# L293DbaseArduVehicle-ElectricalSchematic.net
KiCad netlist of a schematic drawn in Altium Designer
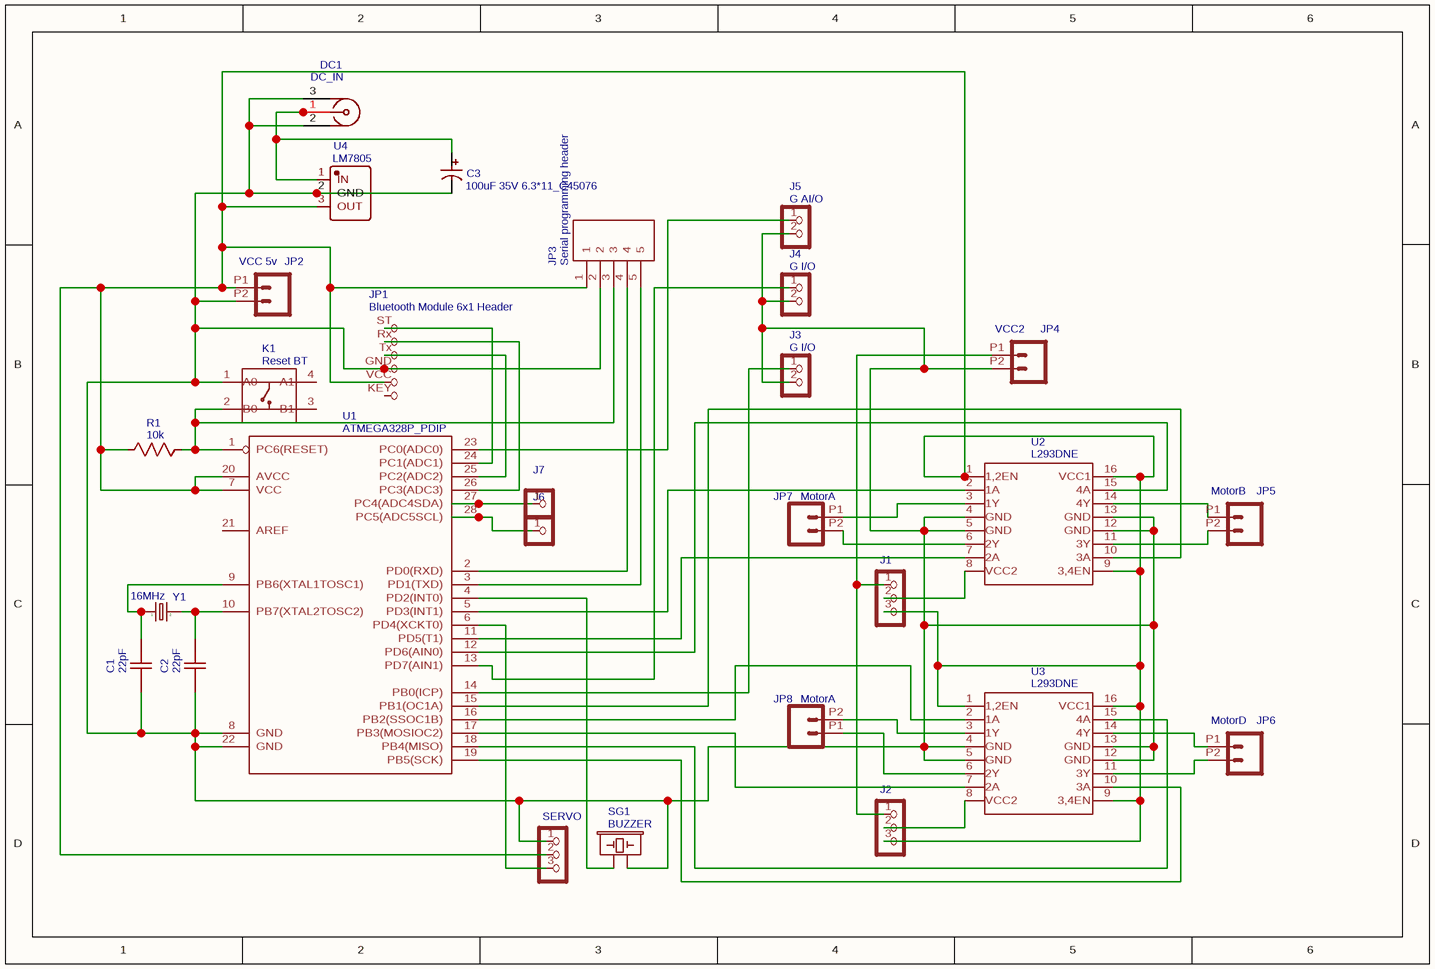
[diagram p0: L293DbaseArduVehicle-ElectricalSchematic_2022-03-31.schdoc]

(export (version "E")
  (design (tool "Eeschema 10.0.6"))
  (components
    (comp (ref "C1")
      (value "22pF")
      (fields (field (name "BOM_MANUFACTURER PART") "?"))
      (libsource (lib "altium-import") (part "root_1_22pF_"))
    )
    (comp (ref "C2")
      (value "22pF")
      (fields (field (name "BOM_MANUFACTURER PART") "?"))
      (libsource (lib "altium-import") (part "root_1_22pF_"))
    )
    (comp (ref "C3")
      (value "100uF 35V 6.3*11_C45076")
      (fields
        (field (name "BOM_SUPPLIER PART") "C45076")
        (field (name "BOM_MANUFACTURER PART") "100uF 35V 6.3*11")
      )
      (libsource (lib "altium-import") (part "root_3_100uF 35V 6.3*11_C45076_"))
    )
    (comp (ref "DC1")
      (value "DC_IN")
      (fields (field (name "BOM_MANUFACTURER PART") "DC005-2.0MM") (field (name "CONTRIBUTOR") "KKHOME生活"))
      (libsource (lib "altium-import") (part "root_0_DC_IN_"))
    )
    (comp (ref "J1")
      (value "CON_HEADER_1X03-PTH")
      (fields (field (name "BOM_MANUFACTURER PART") "?") (field (name "CONTRIBUTOR") "DangerousPrototype"))
      (libsource (lib "altium-import") (part "root_0_CON_HEADER_1X03-PTH_"))
    )
    (comp (ref "J2")
      (value "CON_HEADER_1X03-PTH")
      (fields (field (name "BOM_MANUFACTURER PART") "?") (field (name "CONTRIBUTOR") "DangerousPrototype"))
      (libsource (lib "altium-import") (part "root_0_CON_HEADER_1X03-PTH_"))
    )
    (comp (ref "J3")
      (value "G I/O")
      (fields (field (name "BOM_MANUFACTURER PART") "?") (field (name "CONTRIBUTOR") "DangerousPrototype"))
      (libsource (lib "altium-import") (part "root_0_G I/O_"))
    )
    (comp (ref "J4")
      (value "G I/O")
      (fields (field (name "BOM_MANUFACTURER PART") "?") (field (name "CONTRIBUTOR") "DangerousPrototype"))
      (libsource (lib "altium-import") (part "root_0_G I/O_"))
    )
    (comp (ref "J5")
      (value "G AI/O")
      (fields (field (name "BOM_MANUFACTURER PART") "?") (field (name "CONTRIBUTOR") "DangerousPrototype"))
      (libsource (lib "altium-import") (part "root_0_G AI/O_"))
    )
    (comp (ref "J6")
      (value "CON_HEADER_1X01-PTH")
      (fields (field (name "BOM_MANUFACTURER PART") "?") (field (name "CONTRIBUTOR") "DangerousPrototype"))
      (libsource (lib "altium-import") (part "root_0_CON_HEADER_1X01-PTH_"))
    )
    (comp (ref "J7")
      (value "CON_HEADER_1X01-PTH")
      (fields (field (name "BOM_MANUFACTURER PART") "?") (field (name "CONTRIBUTOR") "DangerousPrototype"))
      (libsource (lib "altium-import") (part "root_0_CON_HEADER_1X01-PTH_"))
    )
    (comp (ref "JP1")
      (value "Bluetooth Module 6x1 Header")
      (description "PIN HEADER")
      (fields (field (name "BOM_MANUFACTURER PART") "?") (field (name "CONTRIBUTOR") "Adafruit"))
      (libsource (lib "altium-import") (part "root_0_Bluetooth Module 6x1 Header_"))
    )
    (comp (ref "JP2")
      (value "VCC 5v")
      (description "Standard 2-pin 0.1 header. Use with")
      (fields (field (name "BOM_MANUFACTURER PART") "?") (field (name "CONTRIBUTOR") "SparkFun"))
      (libsource (lib "altium-import") (part "root_2_VCC 5v_"))
    )
    (comp (ref "JP3")
      (value "Serial programming header")
      (fields (field (name "BOM_MANUFACTURER PART") "?"))
      (libsource (lib "altium-import") (part "root_1_Serial programming header_"))
    )
    (comp (ref "JP4")
      (value "VCC2")
      (description "Standard 2-pin 0.1 header. Use with")
      (fields (field (name "BOM_MANUFACTURER PART") "?") (field (name "CONTRIBUTOR") "SparkFun"))
      (libsource (lib "altium-import") (part "root_2_VCC2_"))
    )
    (comp (ref "JP5")
      (value "MotorB")
      (description "Standard 2-pin 0.1 header. Use with")
      (fields (field (name "BOM_MANUFACTURER PART") "?") (field (name "CONTRIBUTOR") "SparkFun"))
      (libsource (lib "altium-import") (part "root_2_MotorB_"))
    )
    (comp (ref "JP6")
      (value "MotorD")
      (description "Standard 2-pin 0.1 header. Use with")
      (fields (field (name "BOM_MANUFACTURER PART") "?") (field (name "CONTRIBUTOR") "SparkFun"))
      (libsource (lib "altium-import") (part "root_2_MotorD_"))
    )
    (comp (ref "JP7")
      (value "MotorA")
      (description "Standard 2-pin 0.1 header. Use with")
      (fields (field (name "BOM_MANUFACTURER PART") "?") (field (name "CONTRIBUTOR") "SparkFun"))
      (libsource (lib "") (part "root_2_MotorA__1"))
    )
    (comp (ref "JP8")
      (value "MotorA")
      (description "Standard 2-pin 0.1 header. Use with")
      (fields (field (name "BOM_MANUFACTURER PART") "?") (field (name "CONTRIBUTOR") "SparkFun"))
      (libsource (lib "altium-import") (part "root_2_MotorA_"))
    )
    (comp (ref "K1")
      (value "Reset BT")
      (description "SWITCH TACTILE SPST-NO 0.05A 12V")
      (fields (field (name "BOM_MANUFACTURER PART") "TS-1109") (field (name "BOM_SUPPLIER PART") "311020024"))
      (libsource (lib "altium-import") (part "root_0_Reset BT_"))
    )
    (comp (ref "R1")
      (value "10k")
      (fields (field (name "BOM_MANUFACTURER PART") "?"))
      (libsource (lib "altium-import") (part "root_0_10k_"))
    )
    (comp (ref "SERVO")
      (value "CON_HEADER_1X03-PTH")
      (fields (field (name "BOM_MANUFACTURER PART") "?") (field (name "CONTRIBUTOR") "DangerousPrototype"))
      (libsource (lib "altium-import") (part "root_0_CON_HEADER_1X03-PTH_"))
    )
    (comp (ref "SG1")
      (value "BUZZER")
      (fields (field (name "BOM_MANUFACTURER PART") "?") (field (name "CONTRIBUTOR") "SparkFun"))
      (libsource (lib "altium-import") (part "root_0_BUZZER_"))
    )
    (comp (ref "U1")
      (value "ATMEGA328P_PDIP")
      (description "uC used in the Arduino")
      (fields (field (name "BOM_MANUFACTURER PART") "?") (field (name "CONTRIBUTOR") "SparkFun"))
      (libsource (lib "altium-import") (part "root_0_ATMEGA328P_PDIP_"))
    )
    (comp (ref "U2")
      (value "L293DNE")
      (description "DIP IC Driver;")
      (fields (field (name "BOM_SUPPLIER PART") "310040017"))
      (libsource (lib "altium-import") (part "root_0_L293DNE_"))
    )
    (comp (ref "U3")
      (value "L293DNE")
      (description "DIP IC Driver;")
      (fields (field (name "BOM_SUPPLIER PART") "310040017"))
      (libsource (lib "altium-import") (part "root_0_L293DNE_"))
    )
    (comp (ref "U4")
      (value "LM7805")
      (fields (field (name "BOM_SUPPLIER PART") "C845394") (field (name "CONTRIBUTOR") "LCSC"))
      (libsource (lib "altium-import") (part "root_0_LM7805_"))
    )
    (comp (ref "Y1")
      (value "16MHz")
      (description "DIP Crystal 16MHz-18pF-30ppm-40R;")
      (fields
        (field (name "BOM_MANUFACTURER PART") "HC-49US    16.000MHz")
        (field (name "BOM_SUPPLIER PART") "306010014")
      )
      (libsource (lib "altium-import") (part "root_0_16MHz_"))
    )
  )
  (nets
    (net (code "1") (name "Net-(DC1-GND)") (class "Default")
      (node (ref "C1") (pin "1") (pinfunction "1_1") (pintype "passive"))
      (node (ref "C2") (pin "1") (pinfunction "1_1") (pintype "passive"))
      (node (ref "C3") (pin "2") (pinfunction "2_2") (pintype "passive"))
      (node (ref "DC1") (pin "2") (pinfunction "2_2") (pintype "passive"))
      (node (ref "DC1") (pin "3") (pinfunction "GND_3") (pintype "passive"))
      (node (ref "J3") (pin "2") (pinfunction "2_2") (pintype "passive"))
      (node (ref "J4") (pin "2") (pinfunction "2_2") (pintype "passive"))
      (node (ref "J5") (pin "2") (pinfunction "2_2") (pintype "passive"))
      (node (ref "JP1") (pin "GND") (pinfunction "GND_GND") (pintype "passive"))
      (node (ref "JP2") (pin "P2") (pinfunction "2_P2") (pintype "passive"))
      (node (ref "JP3") (pin "2") (pinfunction "2_2") (pintype "passive"))
      (node (ref "JP4") (pin "P2") (pinfunction "2_P2") (pintype "passive"))
      (node (ref "K1") (pin "1") (pinfunction "A0_1") (pintype "passive"))
      (node (ref "SERVO") (pin "1") (pinfunction "1_1") (pintype "passive"))
      (node (ref "SG1") (pin "-") (pinfunction "2_-") (pintype "passive"))
      (node (ref "U1") (pin "22") (pinfunction "GND_22") (pintype "passive"))
      (node (ref "U1") (pin "8") (pinfunction "GND_8") (pintype "passive"))
      (node (ref "U2") (pin "12") (pinfunction "GND_12") (pintype "passive"))
      (node (ref "U2") (pin "13") (pinfunction "GND_13") (pintype "passive"))
      (node (ref "U2") (pin "4") (pinfunction "GND_4") (pintype "passive"))
      (node (ref "U2") (pin "5") (pinfunction "GND_5") (pintype "passive"))
      (node (ref "U3") (pin "12") (pinfunction "GND_12") (pintype "passive"))
      (node (ref "U3") (pin "13") (pinfunction "GND_13") (pintype "passive"))
      (node (ref "U3") (pin "4") (pinfunction "GND_4") (pintype "passive"))
      (node (ref "U3") (pin "5") (pinfunction "GND_5") (pintype "passive"))
      (node (ref "U4") (pin "2") (pinfunction "GND_2") (pintype "passive"))
    )
    (net (code "2") (name "Net-(DC1-VCC)") (class "Default")
      (node (ref "C3") (pin "1") (pinfunction "1_1") (pintype "passive"))
      (node (ref "DC1") (pin "1") (pinfunction "VCC_1") (pintype "passive"))
      (node (ref "U4") (pin "1") (pinfunction "IN_1") (pintype "passive"))
    )
    (net (code "3") (name "Net-(JP2-1)") (class "Default")
      (node (ref "J1") (pin "3") (pinfunction "3_3") (pintype "passive"))
      (node (ref "J2") (pin "3") (pinfunction "3_3") (pintype "passive"))
      (node (ref "JP1") (pin "VCC") (pinfunction "VCC_VCC") (pintype "passive"))
      (node (ref "JP2") (pin "P1") (pinfunction "1_P1") (pintype "passive"))
      (node (ref "JP3") (pin "1") (pinfunction "1_1") (pintype "passive"))
      (node (ref "R1") (pin "1") (pinfunction "1_1") (pintype "passive"))
      (node (ref "SERVO") (pin "2") (pinfunction "2_2") (pintype "passive"))
      (node (ref "U1") (pin "20") (pinfunction "AVCC_20") (pintype "passive"))
      (node (ref "U1") (pin "7") (pinfunction "VCC_7") (pintype "passive"))
      (node (ref "U2") (pin "1") (pinfunction "1,2EN_1") (pintype "passive"))
      (node (ref "U2") (pin "16") (pinfunction "VCC1_16") (pintype "passive"))
      (node (ref "U2") (pin "9") (pinfunction "3,4EN_9") (pintype "passive"))
      (node (ref "U3") (pin "1") (pinfunction "1,2EN_1") (pintype "passive"))
      (node (ref "U3") (pin "16") (pinfunction "VCC1_16") (pintype "passive"))
      (node (ref "U3") (pin "9") (pinfunction "3,4EN_9") (pintype "passive"))
      (node (ref "U4") (pin "3") (pinfunction "OUT_3") (pintype "passive"))
    )
    (net (code "4") (name "Net-(JP4-1)") (class "Default")
      (node (ref "J1") (pin "1") (pinfunction "1_1") (pintype "passive"))
      (node (ref "J2") (pin "1") (pinfunction "1_1") (pintype "passive"))
      (node (ref "JP4") (pin "P1") (pinfunction "1_P1") (pintype "passive"))
    )
    (net (code "5") (name "Net-(JP5-1)") (class "Default")
      (node (ref "JP5") (pin "P1") (pinfunction "1_P1") (pintype "passive"))
      (node (ref "U2") (pin "14") (pinfunction "4Y_14") (pintype "passive"))
    )
    (net (code "6") (name "Net-(JP5-2)") (class "Default")
      (node (ref "JP5") (pin "P2") (pinfunction "2_P2") (pintype "passive"))
      (node (ref "U2") (pin "11") (pinfunction "3Y_11") (pintype "passive"))
    )
    (net (code "7") (name "Net-(JP6-1)") (class "Default")
      (node (ref "JP6") (pin "P1") (pinfunction "1_P1") (pintype "passive"))
      (node (ref "U3") (pin "14") (pinfunction "4Y_14") (pintype "passive"))
    )
    (net (code "8") (name "Net-(JP6-2)") (class "Default")
      (node (ref "JP6") (pin "P2") (pinfunction "2_P2") (pintype "passive"))
      (node (ref "U3") (pin "11") (pinfunction "3Y_11") (pintype "passive"))
    )
    (net (code "9") (name "Net-(JP7-1)") (class "Default")
      (node (ref "JP7") (pin "P1") (pinfunction "1_P1") (pintype "passive"))
      (node (ref "U2") (pin "3") (pinfunction "1Y_3") (pintype "passive"))
    )
    (net (code "10") (name "Net-(JP7-2)") (class "Default")
      (node (ref "JP7") (pin "P2") (pinfunction "2_P2") (pintype "passive"))
      (node (ref "U2") (pin "6") (pinfunction "2Y_6") (pintype "passive"))
    )
    (net (code "11") (name "Net-(JP8-1)") (class "Default")
      (node (ref "JP8") (pin "P2") (pinfunction "1_P2") (pintype "passive"))
      (node (ref "U3") (pin "3") (pinfunction "1Y_3") (pintype "passive"))
    )
    (net (code "12") (name "Net-(JP8-2)") (class "Default")
      (node (ref "JP8") (pin "P1") (pinfunction "2_P1") (pintype "passive"))
      (node (ref "U3") (pin "6") (pinfunction "2Y_6") (pintype "passive"))
    )
    (net (code "13") (name "Net-(K1-B0)") (class "Default")
      (node (ref "JP3") (pin "3") (pinfunction "3_3") (pintype "passive"))
      (node (ref "K1") (pin "2") (pinfunction "B0_2") (pintype "passive"))
      (node (ref "R1") (pin "2") (pinfunction "2_2") (pintype "passive"))
      (node (ref "U1") (pin "1") (pinfunction "PC6(RESET)_1") (pintype "passive"))
    )
    (net (code "14") (name "Net-(SG1-1)") (class "Default")
      (node (ref "SG1") (pin "+") (pinfunction "1_+") (pintype "passive"))
      (node (ref "U1") (pin "4") (pinfunction "PD2(INT0)_4") (pintype "passive"))
    )
    (net (code "15") (name "Net-(U1-PB0(ICP))") (class "Default")
      (node (ref "J3") (pin "1") (pinfunction "1_1") (pintype "passive"))
      (node (ref "U1") (pin "14") (pinfunction "PB0(ICP)_14") (pintype "passive"))
    )
    (net (code "16") (name "Net-(U1-PB1(OC1A))") (class "Default")
      (node (ref "U1") (pin "15") (pinfunction "PB1(OC1A)_15") (pintype "passive"))
      (node (ref "U2") (pin "10") (pinfunction "3A_10") (pintype "passive"))
    )
    (net (code "17") (name "Net-(U1-PB2(SSOC1B))") (class "Default")
      (node (ref "U1") (pin "16") (pinfunction "PB2(SSOC1B)_16") (pintype "passive"))
      (node (ref "U3") (pin "2") (pinfunction "1A_2") (pintype "passive"))
    )
    (net (code "18") (name "Net-(U1-PB3(MOSIOC2))") (class "Default")
      (node (ref "U1") (pin "17") (pinfunction "PB3(MOSIOC2)_17") (pintype "passive"))
      (node (ref "U3") (pin "7") (pinfunction "2A_7") (pintype "passive"))
    )
    (net (code "19") (name "Net-(U1-PB4(MISO))") (class "Default")
      (node (ref "U1") (pin "18") (pinfunction "PB4(MISO)_18") (pintype "passive"))
      (node (ref "U3") (pin "15") (pinfunction "4A_15") (pintype "passive"))
    )
    (net (code "20") (name "Net-(U1-PB5(SCK))") (class "Default")
      (node (ref "U1") (pin "19") (pinfunction "PB5(SCK)_19") (pintype "passive"))
      (node (ref "U3") (pin "10") (pinfunction "3A_10") (pintype "passive"))
    )
    (net (code "21") (name "Net-(U1-PB6(XTAL1TOSC1))") (class "Default")
      (node (ref "C1") (pin "2") (pinfunction "2_2") (pintype "passive"))
      (node (ref "U1") (pin "9") (pinfunction "PB6(XTAL1TOSC1)_9") (pintype "passive"))
      (node (ref "Y1") (pin "1") (pinfunction "1_1") (pintype "passive"))
    )
    (net (code "22") (name "Net-(U1-PB7(XTAL2TOSC2))") (class "Default")
      (node (ref "C2") (pin "2") (pinfunction "2_2") (pintype "passive"))
      (node (ref "U1") (pin "10") (pinfunction "PB7(XTAL2TOSC2)_10") (pintype "passive"))
      (node (ref "Y1") (pin "2") (pinfunction "2_2") (pintype "passive"))
    )
    (net (code "23") (name "Net-(U1-PC0(ADC0))") (class "Default")
      (node (ref "J5") (pin "1") (pinfunction "1_1") (pintype "passive"))
      (node (ref "U1") (pin "23") (pinfunction "PC0(ADC0)_23") (pintype "passive"))
    )
    (net (code "24") (name "Net-(U1-PC1(ADC1))") (class "Default")
      (node (ref "JP1") (pin "ST") (pinfunction "ST_ST") (pintype "passive"))
      (node (ref "U1") (pin "24") (pinfunction "PC1(ADC1)_24") (pintype "passive"))
    )
    (net (code "25") (name "Net-(U1-PC2(ADC2))") (class "Default")
      (node (ref "JP1") (pin "Tx") (pinfunction "Tx_Tx") (pintype "passive"))
      (node (ref "U1") (pin "25") (pinfunction "PC2(ADC2)_25") (pintype "passive"))
    )
    (net (code "26") (name "Net-(U1-PC3(ADC3))") (class "Default")
      (node (ref "JP1") (pin "Rx") (pinfunction "Rx_Rx") (pintype "passive"))
      (node (ref "U1") (pin "26") (pinfunction "PC3(ADC3)_26") (pintype "passive"))
    )
    (net (code "27") (name "Net-(U1-PC4(ADC4SDA))") (class "Default")
      (node (ref "J7") (pin "1") (pinfunction "1_1") (pintype "passive"))
      (node (ref "U1") (pin "27") (pinfunction "PC4(ADC4SDA)_27") (pintype "passive"))
    )
    (net (code "28") (name "Net-(U1-PC5(ADC5SCL))") (class "Default")
      (node (ref "J6") (pin "1") (pinfunction "1_1") (pintype "passive"))
      (node (ref "U1") (pin "28") (pinfunction "PC5(ADC5SCL)_28") (pintype "passive"))
    )
    (net (code "29") (name "Net-(U1-PD0(RXD))") (class "Default")
      (node (ref "JP3") (pin "4") (pinfunction "4_4") (pintype "passive"))
      (node (ref "U1") (pin "2") (pinfunction "PD0(RXD)_2") (pintype "passive"))
    )
    (net (code "30") (name "Net-(U1-PD1(TXD))") (class "Default")
      (node (ref "JP3") (pin "5") (pinfunction "5_5") (pintype "passive"))
      (node (ref "U1") (pin "3") (pinfunction "PD1(TXD)_3") (pintype "passive"))
    )
    (net (code "31") (name "Net-(U1-PD3(INT1))") (class "Default")
      (node (ref "U1") (pin "5") (pinfunction "PD3(INT1)_5") (pintype "passive"))
      (node (ref "U2") (pin "2") (pinfunction "1A_2") (pintype "passive"))
    )
    (net (code "32") (name "Net-(U1-PD4(XCKT0))") (class "Default")
      (node (ref "SERVO") (pin "3") (pinfunction "3_3") (pintype "passive"))
      (node (ref "U1") (pin "6") (pinfunction "PD4(XCKT0)_6") (pintype "passive"))
    )
    (net (code "33") (name "Net-(U1-PD5(T1))") (class "Default")
      (node (ref "U1") (pin "11") (pinfunction "PD5(T1)_11") (pintype "passive"))
      (node (ref "U2") (pin "7") (pinfunction "2A_7") (pintype "passive"))
    )
    (net (code "34") (name "Net-(U1-PD6(AIN0))") (class "Default")
      (node (ref "U1") (pin "12") (pinfunction "PD6(AIN0)_12") (pintype "passive"))
      (node (ref "U2") (pin "15") (pinfunction "4A_15") (pintype "passive"))
    )
    (net (code "35") (name "Net-(U1-PD7(AIN1))") (class "Default")
      (node (ref "J4") (pin "1") (pinfunction "1_1") (pintype "passive"))
      (node (ref "U1") (pin "13") (pinfunction "PD7(AIN1)_13") (pintype "passive"))
    )
    (net (code "36") (name "Net-(U2-VCC2)") (class "Default")
      (node (ref "J1") (pin "2") (pinfunction "2_2") (pintype "passive"))
      (node (ref "U2") (pin "8") (pinfunction "VCC2_8") (pintype "passive"))
    )
    (net (code "37") (name "Net-(U3-VCC2)") (class "Default")
      (node (ref "J2") (pin "2") (pinfunction "2_2") (pintype "passive"))
      (node (ref "U3") (pin "8") (pinfunction "VCC2_8") (pintype "passive"))
    )
    (net (code "38") (name "unconnected-(JP1-PadKEY)") (class "Default")
      (node (ref "JP1") (pin "KEY") (pinfunction "KEY_KEY") (pintype "passive"))
    )
    (net (code "39") (name "unconnected-(K1-A1-Pad4)") (class "Default")
      (node (ref "K1") (pin "4") (pinfunction "A1_4") (pintype "passive"))
    )
    (net (code "40") (name "unconnected-(K1-B1-Pad3)") (class "Default")
      (node (ref "K1") (pin "3") (pinfunction "B1_3") (pintype "passive"))
    )
    (net (code "41") (name "unconnected-(U1-AREF-Pad21)") (class "Default")
      (node (ref "U1") (pin "21") (pinfunction "AREF_21") (pintype "passive"))
    )
  )
)
